# BBB-SPI-FF-Cape-0907.net
KiCad netlist of a schematic drawn in EAGLE
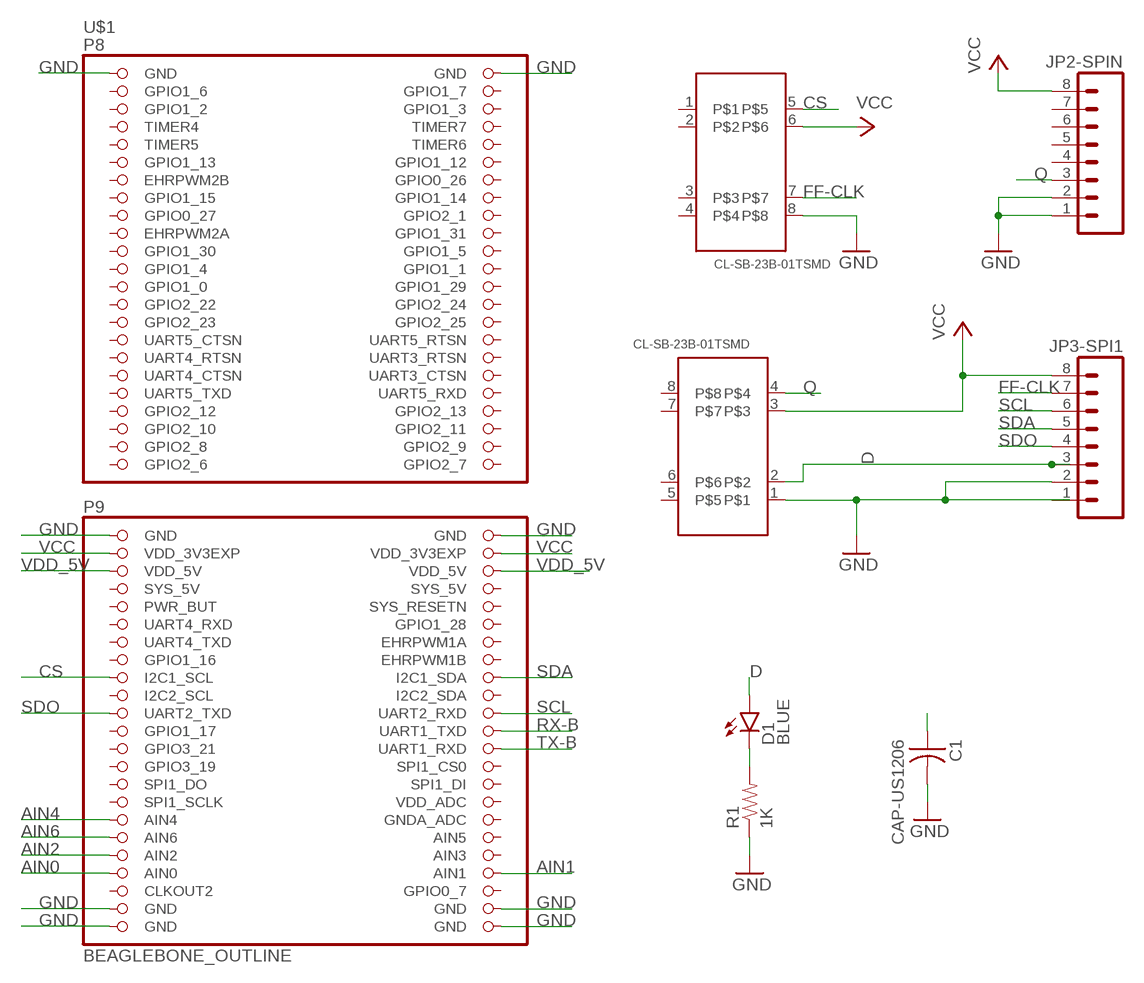
[diagram p0: schematic, sheet 1]

(export (version "E")
  (design (tool "Eeschema 10.0.6"))
  (components
    (comp (ref "C1")
      (value "CAP-US1206")
      (footprint "eagle-import:C1206")
      (libsource (lib "eagle-import") (part "CAP-US1206"))
    )
    (comp (ref "D1")
      (value "BLUE")
      (footprint "eagle-import:LED-1206")
      (libsource (lib "eagle-import") (part "LED-BLUE1206"))
    )
    (comp (ref "JP2-SPIN")
      (value "M08BM08B-SRSS-TB")
      (footprint "eagle-import:BM08B-SRSS-TB")
      (libsource (lib "eagle-import") (part "M08BM08B-SRSS-TB"))
    )
    (comp (ref "JP3-SPI1")
      (value "M08BM08B-SRSS-TB")
      (footprint "eagle-import:BM08B-SRSS-TB")
      (libsource (lib "eagle-import") (part "M08BM08B-SRSS-TB"))
    )
    (comp (ref "R1")
      (value "1K")
      (footprint "eagle-import:1206")
      (libsource (lib "eagle-import") (part "RESISTOR1206"))
    )
    (comp (ref "U$1")
      (value "BEAGLEBONE_OUTLINE")
      (footprint "eagle-import:BEAGLEBONE_SHIELD")
      (libsource (lib "eagle-import") (part "BEAGLEBONE_OUTLINE"))
    )
    (comp (ref "U$2")
      (value "CL-SB-23B-01TSMD")
      (footprint "eagle-import:CL-SB-23B")
      (libsource (lib "eagle-import") (part "CL-SB-23B-01TSMD"))
    )
    (comp (ref "U$3")
      (value "CL-SB-23B-01TSMD")
      (footprint "eagle-import:CL-SB-23B")
      (libsource (lib "eagle-import") (part "CL-SB-23B-01TSMD"))
    )
  )
  (nets
    (net (code "1") (name "/AIN0") (class "Default")
      (node (ref "U$1") (pin "85") (pinfunction "AIN0_85") (pintype "power_in"))
    )
    (net (code "2") (name "/AIN1") (class "Default")
      (node (ref "U$1") (pin "86") (pinfunction "AIN1_86") (pintype "passive"))
    )
    (net (code "3") (name "/AIN2") (class "Default")
      (node (ref "U$1") (pin "83") (pinfunction "AIN2_83") (pintype "passive"))
    )
    (net (code "4") (name "/AIN4") (class "Default")
      (node (ref "U$1") (pin "79") (pinfunction "AIN4_79") (pintype "passive"))
    )
    (net (code "5") (name "/AIN6") (class "Default")
      (node (ref "U$1") (pin "81") (pinfunction "AIN6_81") (pintype "passive"))
    )
    (net (code "6") (name "/CS") (class "Default")
      (node (ref "U$1") (pin "63") (pinfunction "I2C1_SCL_63") (pintype "passive"))
      (node (ref "U$2") (pin "5") (pinfunction "P$5_5") (pintype "bidirectional"))
    )
    (net (code "7") (name "/D") (class "Default")
      (node (ref "D1") (pin "A") (pinfunction "A_A") (pintype "passive"))
      (node (ref "JP3-SPI1") (pin "3") (pinfunction "3_3") (pintype "passive"))
      (node (ref "U$3") (pin "2") (pinfunction "P$2_2") (pintype "bidirectional"))
    )
    (net (code "8") (name "/FF-CLK") (class "Default")
      (node (ref "C1") (pin "1") (pinfunction "1_1") (pintype "passive"))
      (node (ref "JP3-SPI1") (pin "7") (pinfunction "7_7") (pintype "passive"))
      (node (ref "U$2") (pin "7") (pinfunction "P$7_7") (pintype "bidirectional"))
    )
    (net (code "9") (name "/Q") (class "Default")
      (node (ref "JP2-SPIN") (pin "3") (pinfunction "3_3") (pintype "passive"))
      (node (ref "U$3") (pin "4") (pinfunction "P$4_4") (pintype "bidirectional"))
    )
    (net (code "10") (name "/RX-B") (class "Default")
      (node (ref "U$1") (pin "70") (pinfunction "UART1_TXD_70") (pintype "passive"))
    )
    (net (code "11") (name "/SCL") (class "Default")
      (node (ref "JP3-SPI1") (pin "6") (pinfunction "6_6") (pintype "passive"))
      (node (ref "U$1") (pin "68") (pinfunction "UART2_RXD_68") (pintype "passive"))
    )
    (net (code "12") (name "/SDA") (class "Default")
      (node (ref "JP3-SPI1") (pin "5") (pinfunction "5_5") (pintype "passive"))
      (node (ref "U$1") (pin "64") (pinfunction "I2C1_SDA_64") (pintype "passive"))
    )
    (net (code "13") (name "/SDO") (class "Default")
      (node (ref "JP3-SPI1") (pin "4") (pinfunction "4_4") (pintype "passive"))
      (node (ref "U$1") (pin "67") (pinfunction "UART2_TXD_67") (pintype "passive"))
    )
    (net (code "14") (name "/SYS_5V") (class "Default")
      (node (ref "U$1") (pin "53") (pinfunction "SYS_5V_53") (pintype "power_in"))
    )
    (net (code "15") (name "/TX-B") (class "Default")
      (node (ref "U$1") (pin "72") (pinfunction "UART1_RXD_72") (pintype "passive"))
    )
    (net (code "16") (name "/VDD_5V") (class "Default")
      (node (ref "U$1") (pin "51") (pinfunction "VDD_5V_51") (pintype "power_in"))
      (node (ref "U$1") (pin "52") (pinfunction "VDD_5V_52") (pintype "power_in"))
    )
    (net (code "17") (name "GND") (class "Default")
      (node (ref "C1") (pin "2") (pinfunction "2_2") (pintype "passive"))
      (node (ref "JP2-SPIN") (pin "1") (pinfunction "1_1") (pintype "passive"))
      (node (ref "JP2-SPIN") (pin "2") (pinfunction "2_2") (pintype "passive"))
      (node (ref "JP3-SPI1") (pin "2") (pinfunction "2_2") (pintype "passive"))
      (node (ref "R1") (pin "1") (pinfunction "1_1") (pintype "passive"))
      (node (ref "U$1") (pin "1") (pinfunction "GND_1") (pintype "power_in"))
      (node (ref "U$1") (pin "2") (pinfunction "GND_2") (pintype "power_in"))
      (node (ref "U$1") (pin "47") (pinfunction "GND_47") (pintype "power_in"))
      (node (ref "U$1") (pin "48") (pinfunction "GND_48") (pintype "power_in"))
      (node (ref "U$1") (pin "89") (pinfunction "GND_89") (pintype "power_in"))
      (node (ref "U$1") (pin "90") (pinfunction "GND_90") (pintype "power_in"))
      (node (ref "U$1") (pin "91") (pinfunction "GND_91") (pintype "power_in"))
      (node (ref "U$1") (pin "92") (pinfunction "GND_92") (pintype "power_in"))
      (node (ref "U$2") (pin "8") (pinfunction "P$8_8") (pintype "bidirectional"))
      (node (ref "U$3") (pin "1") (pinfunction "P$1_1") (pintype "bidirectional"))
    )
    (net (code "18") (name "Net-(D1-PadC)") (class "Default")
      (node (ref "D1") (pin "C") (pinfunction "C_C") (pintype "passive"))
      (node (ref "R1") (pin "2") (pinfunction "2_2") (pintype "passive"))
    )
    (net (code "19") (name "VCC") (class "Default")
      (node (ref "JP2-SPIN") (pin "8") (pinfunction "8_8") (pintype "passive"))
      (node (ref "JP3-SPI1") (pin "8") (pinfunction "8_8") (pintype "passive"))
      (node (ref "U$1") (pin "49") (pinfunction "VDD_3V3EXP_49") (pintype "power_in"))
      (node (ref "U$1") (pin "50") (pinfunction "VDD_3V3EXP_50") (pintype "power_in"))
      (node (ref "U$2") (pin "6") (pinfunction "P$6_6") (pintype "bidirectional"))
      (node (ref "U$3") (pin "3") (pinfunction "P$3_3") (pintype "bidirectional"))
    )
    (net (code "20") (name "unconnected-(JP2-SPIN-Pad4)") (class "Default")
      (node (ref "JP2-SPIN") (pin "4") (pinfunction "4_4") (pintype "passive"))
    )
    (net (code "21") (name "unconnected-(JP2-SPIN-Pad5)") (class "Default")
      (node (ref "JP2-SPIN") (pin "5") (pinfunction "5_5") (pintype "passive"))
    )
    (net (code "22") (name "unconnected-(JP2-SPIN-Pad6)") (class "Default")
      (node (ref "JP2-SPIN") (pin "6") (pinfunction "6_6") (pintype "passive"))
    )
    (net (code "23") (name "unconnected-(JP2-SPIN-Pad7)") (class "Default")
      (node (ref "JP2-SPIN") (pin "7") (pinfunction "7_7") (pintype "passive"))
    )
    (net (code "24") (name "unconnected-(JP3-SPI1-Pad1)") (class "Default")
      (node (ref "JP3-SPI1") (pin "1") (pinfunction "1_1") (pintype "passive"))
    )
    (net (code "25") (name "unconnected-(U$1-AIN3-Pad84)") (class "Default")
      (node (ref "U$1") (pin "84") (pinfunction "AIN3_84") (pintype "passive"))
    )
    (net (code "26") (name "unconnected-(U$1-AIN5-Pad82)") (class "Default")
      (node (ref "U$1") (pin "82") (pinfunction "AIN5_82") (pintype "passive"))
    )
    (net (code "27") (name "unconnected-(U$1-CLKOUT2-Pad87)") (class "Default")
      (node (ref "U$1") (pin "87") (pinfunction "CLKOUT2_87") (pintype "input"))
    )
    (net (code "28") (name "unconnected-(U$1-EHRPWM1A-Pad60)") (class "Default")
      (node (ref "U$1") (pin "60") (pinfunction "EHRPWM1A_60") (pintype "passive"))
    )
    (net (code "29") (name "unconnected-(U$1-EHRPWM1B-Pad62)") (class "Default")
      (node (ref "U$1") (pin "62") (pinfunction "EHRPWM1B_62") (pintype "passive"))
    )
    (net (code "30") (name "unconnected-(U$1-EHRPWM2A-Pad19)") (class "Default")
      (node (ref "U$1") (pin "19") (pinfunction "EHRPWM2A_19") (pintype "passive"))
    )
    (net (code "31") (name "unconnected-(U$1-EHRPWM2B-Pad13)") (class "Default")
      (node (ref "U$1") (pin "13") (pinfunction "EHRPWM2B_13") (pintype "passive"))
    )
    (net (code "32") (name "unconnected-(U$1-GNDA_ADC-Pad80)") (class "Default")
      (node (ref "U$1") (pin "80") (pinfunction "GNDA_ADC_80") (pintype "passive"))
    )
    (net (code "33") (name "unconnected-(U$1-GPIO0_7-Pad88)") (class "Default")
      (node (ref "U$1") (pin "88") (pinfunction "GPIO0_7_88") (pintype "passive"))
    )
    (net (code "34") (name "unconnected-(U$1-GPIO0_26-Pad14)") (class "Default")
      (node (ref "U$1") (pin "14") (pinfunction "GPIO0_26_14") (pintype "passive"))
    )
    (net (code "35") (name "unconnected-(U$1-GPIO0_27-Pad17)") (class "Default")
      (node (ref "U$1") (pin "17") (pinfunction "GPIO0_27_17") (pintype "passive"))
    )
    (net (code "36") (name "unconnected-(U$1-GPIO1_0-Pad25)") (class "Default")
      (node (ref "U$1") (pin "25") (pinfunction "GPIO1_0_25") (pintype "passive"))
    )
    (net (code "37") (name "unconnected-(U$1-GPIO1_1-Pad24)") (class "Default")
      (node (ref "U$1") (pin "24") (pinfunction "GPIO1_1_24") (pintype "passive"))
    )
    (net (code "38") (name "unconnected-(U$1-GPIO1_2-Pad5)") (class "Default")
      (node (ref "U$1") (pin "5") (pinfunction "GPIO1_2_5") (pintype "passive"))
    )
    (net (code "39") (name "unconnected-(U$1-GPIO1_3-Pad6)") (class "Default")
      (node (ref "U$1") (pin "6") (pinfunction "GPIO1_3_6") (pintype "passive"))
    )
    (net (code "40") (name "unconnected-(U$1-GPIO1_4-Pad23)") (class "Default")
      (node (ref "U$1") (pin "23") (pinfunction "GPIO1_4_23") (pintype "passive"))
    )
    (net (code "41") (name "unconnected-(U$1-GPIO1_5-Pad22)") (class "Default")
      (node (ref "U$1") (pin "22") (pinfunction "GPIO1_5_22") (pintype "passive"))
    )
    (net (code "42") (name "unconnected-(U$1-GPIO1_6-Pad3)") (class "Default")
      (node (ref "U$1") (pin "3") (pinfunction "GPIO1_6_3") (pintype "passive"))
    )
    (net (code "43") (name "unconnected-(U$1-GPIO1_7-Pad4)") (class "Default")
      (node (ref "U$1") (pin "4") (pinfunction "GPIO1_7_4") (pintype "passive"))
    )
    (net (code "44") (name "unconnected-(U$1-GPIO1_12-Pad12)") (class "Default")
      (node (ref "U$1") (pin "12") (pinfunction "GPIO1_12_12") (pintype "passive"))
    )
    (net (code "45") (name "unconnected-(U$1-GPIO1_13-Pad11)") (class "Default")
      (node (ref "U$1") (pin "11") (pinfunction "GPIO1_13_11") (pintype "passive"))
    )
    (net (code "46") (name "unconnected-(U$1-GPIO1_14-Pad16)") (class "Default")
      (node (ref "U$1") (pin "16") (pinfunction "GPIO1_14_16") (pintype "passive"))
    )
    (net (code "47") (name "unconnected-(U$1-GPIO1_15-Pad15)") (class "Default")
      (node (ref "U$1") (pin "15") (pinfunction "GPIO1_15_15") (pintype "passive"))
    )
    (net (code "48") (name "unconnected-(U$1-GPIO1_16-Pad61)") (class "Default")
      (node (ref "U$1") (pin "61") (pinfunction "GPIO1_16_61") (pintype "passive"))
    )
    (net (code "49") (name "unconnected-(U$1-GPIO1_17-Pad69)") (class "Default")
      (node (ref "U$1") (pin "69") (pinfunction "GPIO1_17_69") (pintype "passive"))
    )
    (net (code "50") (name "unconnected-(U$1-GPIO1_28-Pad58)") (class "Default")
      (node (ref "U$1") (pin "58") (pinfunction "GPIO1_28_58") (pintype "passive"))
    )
    (net (code "51") (name "unconnected-(U$1-GPIO1_29-Pad26)") (class "Default")
      (node (ref "U$1") (pin "26") (pinfunction "GPIO1_29_26") (pintype "passive"))
    )
    (net (code "52") (name "unconnected-(U$1-GPIO1_30-Pad21)") (class "Default")
      (node (ref "U$1") (pin "21") (pinfunction "GPIO1_30_21") (pintype "passive"))
    )
    (net (code "53") (name "unconnected-(U$1-GPIO1_31-Pad20)") (class "Default")
      (node (ref "U$1") (pin "20") (pinfunction "GPIO1_31_20") (pintype "passive"))
    )
    (net (code "54") (name "unconnected-(U$1-GPIO2_1-Pad18)") (class "Default")
      (node (ref "U$1") (pin "18") (pinfunction "GPIO2_1_18") (pintype "passive"))
    )
    (net (code "55") (name "unconnected-(U$1-GPIO2_6-Pad45)") (class "Default")
      (node (ref "U$1") (pin "45") (pinfunction "GPIO2_6_45") (pintype "passive"))
    )
    (net (code "56") (name "unconnected-(U$1-GPIO2_7-Pad46)") (class "Default")
      (node (ref "U$1") (pin "46") (pinfunction "GPIO2_7_46") (pintype "passive"))
    )
    (net (code "57") (name "unconnected-(U$1-GPIO2_8-Pad43)") (class "Default")
      (node (ref "U$1") (pin "43") (pinfunction "GPIO2_8_43") (pintype "passive"))
    )
    (net (code "58") (name "unconnected-(U$1-GPIO2_9-Pad44)") (class "Default")
      (node (ref "U$1") (pin "44") (pinfunction "GPIO2_9_44") (pintype "passive"))
    )
    (net (code "59") (name "unconnected-(U$1-GPIO2_10-Pad41)") (class "Default")
      (node (ref "U$1") (pin "41") (pinfunction "GPIO2_10_41") (pintype "passive"))
    )
    (net (code "60") (name "unconnected-(U$1-GPIO2_11-Pad42)") (class "Default")
      (node (ref "U$1") (pin "42") (pinfunction "GPIO2_11_42") (pintype "passive"))
    )
    (net (code "61") (name "unconnected-(U$1-GPIO2_12-Pad39)") (class "Default")
      (node (ref "U$1") (pin "39") (pinfunction "GPIO2_12_39") (pintype "passive"))
    )
    (net (code "62") (name "unconnected-(U$1-GPIO2_13-Pad40)") (class "Default")
      (node (ref "U$1") (pin "40") (pinfunction "GPIO2_13_40") (pintype "passive"))
    )
    (net (code "63") (name "unconnected-(U$1-GPIO2_22-Pad27)") (class "Default")
      (node (ref "U$1") (pin "27") (pinfunction "GPIO2_22_27") (pintype "passive"))
    )
    (net (code "64") (name "unconnected-(U$1-GPIO2_23-Pad29)") (class "Default")
      (node (ref "U$1") (pin "29") (pinfunction "GPIO2_23_29") (pintype "passive"))
    )
    (net (code "65") (name "unconnected-(U$1-GPIO2_24-Pad28)") (class "Default")
      (node (ref "U$1") (pin "28") (pinfunction "GPIO2_24_28") (pintype "passive"))
    )
    (net (code "66") (name "unconnected-(U$1-GPIO2_25-Pad30)") (class "Default")
      (node (ref "U$1") (pin "30") (pinfunction "GPIO2_25_30") (pintype "passive"))
    )
    (net (code "67") (name "unconnected-(U$1-GPIO3_19-Pad73)") (class "Default")
      (node (ref "U$1") (pin "73") (pinfunction "GPIO3_19_73") (pintype "passive"))
    )
    (net (code "68") (name "unconnected-(U$1-GPIO3_21-Pad71)") (class "Default")
      (node (ref "U$1") (pin "71") (pinfunction "GPIO3_21_71") (pintype "passive"))
    )
    (net (code "69") (name "unconnected-(U$1-I2C2_SCL-Pad65)") (class "Default")
      (node (ref "U$1") (pin "65") (pinfunction "I2C2_SCL_65") (pintype "passive"))
    )
    (net (code "70") (name "unconnected-(U$1-I2C2_SDA-Pad66)") (class "Default")
      (node (ref "U$1") (pin "66") (pinfunction "I2C2_SDA_66") (pintype "passive"))
    )
    (net (code "71") (name "unconnected-(U$1-PWR_BUT-Pad55)") (class "Default")
      (node (ref "U$1") (pin "55") (pinfunction "PWR_BUT_55") (pintype "passive"))
    )
    (net (code "72") (name "unconnected-(U$1-SPI1_CS0-Pad74)") (class "Default")
      (node (ref "U$1") (pin "74") (pinfunction "SPI1_CS0_74") (pintype "passive"))
    )
    (net (code "73") (name "unconnected-(U$1-SPI1_DI-Pad76)") (class "Default")
      (node (ref "U$1") (pin "76") (pinfunction "SPI1_DI_76") (pintype "passive"))
    )
    (net (code "74") (name "unconnected-(U$1-SPI1_DO-Pad75)") (class "Default")
      (node (ref "U$1") (pin "75") (pinfunction "SPI1_DO_75") (pintype "passive"))
    )
    (net (code "75") (name "unconnected-(U$1-SPI1_SCLK-Pad77)") (class "Default")
      (node (ref "U$1") (pin "77") (pinfunction "SPI1_SCLK_77") (pintype "passive"))
    )
    (net (code "76") (name "unconnected-(U$1-SYS_5V-Pad54)") (class "Default")
      (node (ref "U$1") (pin "54") (pinfunction "SYS_5V_54") (pintype "passive"))
    )
    (net (code "77") (name "unconnected-(U$1-SYS_RESETN-Pad56)") (class "Default")
      (node (ref "U$1") (pin "56") (pinfunction "SYS_RESETN_56") (pintype "passive"))
    )
    (net (code "78") (name "unconnected-(U$1-TIMER4-Pad7)") (class "Default")
      (node (ref "U$1") (pin "7") (pinfunction "TIMER4_7") (pintype "passive"))
    )
    (net (code "79") (name "unconnected-(U$1-TIMER5-Pad9)") (class "Default")
      (node (ref "U$1") (pin "9") (pinfunction "TIMER5_9") (pintype "passive"))
    )
    (net (code "80") (name "unconnected-(U$1-TIMER6-Pad10)") (class "Default")
      (node (ref "U$1") (pin "10") (pinfunction "TIMER6_10") (pintype "passive"))
    )
    (net (code "81") (name "unconnected-(U$1-TIMER7-Pad8)") (class "Default")
      (node (ref "U$1") (pin "8") (pinfunction "TIMER7_8") (pintype "passive"))
    )
    (net (code "82") (name "unconnected-(U$1-UART3_CTSN-Pad36)") (class "Default")
      (node (ref "U$1") (pin "36") (pinfunction "UART3_CTSN_36") (pintype "passive"))
    )
    (net (code "83") (name "unconnected-(U$1-UART3_RTSN-Pad34)") (class "Default")
      (node (ref "U$1") (pin "34") (pinfunction "UART3_RTSN_34") (pintype "passive"))
    )
    (net (code "84") (name "unconnected-(U$1-UART4_CTSN-Pad35)") (class "Default")
      (node (ref "U$1") (pin "35") (pinfunction "UART4_CTSN_35") (pintype "passive"))
    )
    (net (code "85") (name "unconnected-(U$1-UART4_RTSN-Pad33)") (class "Default")
      (node (ref "U$1") (pin "33") (pinfunction "UART4_RTSN_33") (pintype "passive"))
    )
    (net (code "86") (name "unconnected-(U$1-UART4_RXD-Pad57)") (class "Default")
      (node (ref "U$1") (pin "57") (pinfunction "UART4_RXD_57") (pintype "passive"))
    )
    (net (code "87") (name "unconnected-(U$1-UART4_TXD-Pad59)") (class "Default")
      (node (ref "U$1") (pin "59") (pinfunction "UART4_TXD_59") (pintype "passive"))
    )
    (net (code "88") (name "unconnected-(U$1-UART5_CTSN-Pad31)") (class "Default")
      (node (ref "U$1") (pin "31") (pinfunction "UART5_CTSN_31") (pintype "passive"))
    )
    (net (code "89") (name "unconnected-(U$1-UART5_RTSN-Pad32)") (class "Default")
      (node (ref "U$1") (pin "32") (pinfunction "UART5_RTSN_32") (pintype "passive"))
    )
    (net (code "90") (name "unconnected-(U$1-UART5_RXD-Pad38)") (class "Default")
      (node (ref "U$1") (pin "38") (pinfunction "UART5_RXD_38") (pintype "passive"))
    )
    (net (code "91") (name "unconnected-(U$1-UART5_TXD-Pad37)") (class "Default")
      (node (ref "U$1") (pin "37") (pinfunction "UART5_TXD_37") (pintype "passive"))
    )
    (net (code "92") (name "unconnected-(U$1-VDD_ADC-Pad78)") (class "Default")
      (node (ref "U$1") (pin "78") (pinfunction "VDD_ADC_78") (pintype "passive"))
    )
    (net (code "93") (name "unconnected-(U$2-P$1-Pad1)") (class "Default")
      (node (ref "U$2") (pin "1") (pinfunction "P$1_1") (pintype "bidirectional"))
    )
    (net (code "94") (name "unconnected-(U$2-P$2-Pad2)") (class "Default")
      (node (ref "U$2") (pin "2") (pinfunction "P$2_2") (pintype "bidirectional"))
    )
    (net (code "95") (name "unconnected-(U$2-P$3-Pad3)") (class "Default")
      (node (ref "U$2") (pin "3") (pinfunction "P$3_3") (pintype "bidirectional"))
    )
    (net (code "96") (name "unconnected-(U$2-P$4-Pad4)") (class "Default")
      (node (ref "U$2") (pin "4") (pinfunction "P$4_4") (pintype "bidirectional"))
    )
    (net (code "97") (name "unconnected-(U$3-P$5-Pad5)") (class "Default")
      (node (ref "U$3") (pin "5") (pinfunction "P$5_5") (pintype "bidirectional"))
    )
    (net (code "98") (name "unconnected-(U$3-P$6-Pad6)") (class "Default")
      (node (ref "U$3") (pin "6") (pinfunction "P$6_6") (pintype "bidirectional"))
    )
    (net (code "99") (name "unconnected-(U$3-P$7-Pad7)") (class "Default")
      (node (ref "U$3") (pin "7") (pinfunction "P$7_7") (pintype "bidirectional"))
    )
    (net (code "100") (name "unconnected-(U$3-P$8-Pad8)") (class "Default")
      (node (ref "U$3") (pin "8") (pinfunction "P$8_8") (pintype "bidirectional"))
    )
  )
)
